# table3.net
KiCad netlist of a schematic drawn in EasyEDA
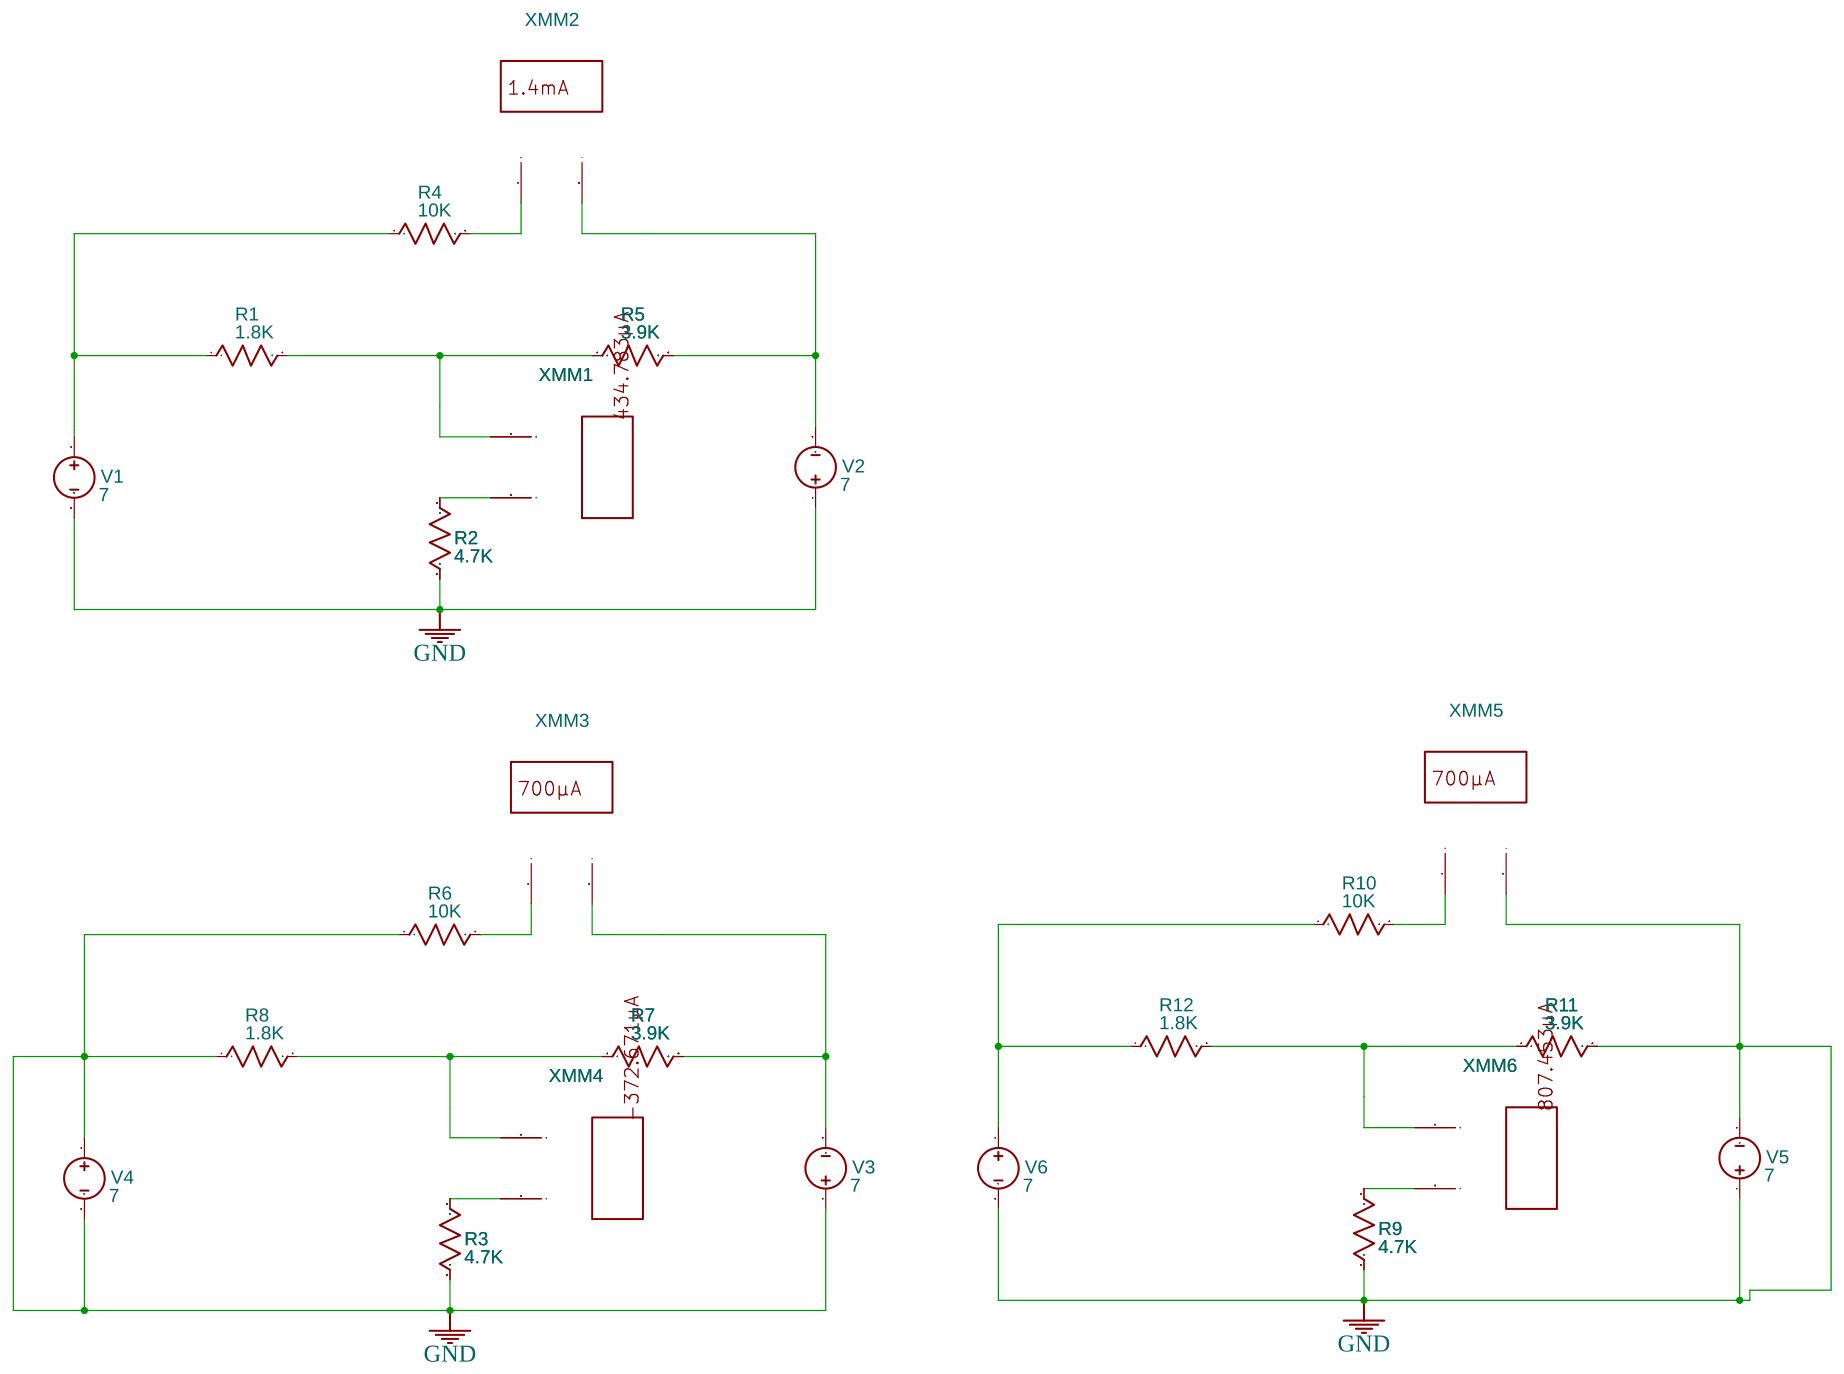
[diagram p0: schematic sheet]

(export (version "E")
  (design (tool "Eeschema 10.0.6"))
  (components
    (comp (ref "R1") (value "1.8K") (libsource (lib "") (part "Resistor_US")))
    (comp (ref "R2") (value "4.7K") (libsource (lib "") (part "Resistor_US_1")))
    (comp (ref "R3") (value "4.7K") (libsource (lib "") (part "Resistor_US_1")))
    (comp (ref "R4") (value "10K") (libsource (lib "") (part "Resistor_US")))
    (comp (ref "R5") (value "3.9K") (libsource (lib "") (part "Resistor_US")))
    (comp (ref "R6") (value "10K") (libsource (lib "") (part "Resistor_US")))
    (comp (ref "R7") (value "3.9K") (libsource (lib "") (part "Resistor_US")))
    (comp (ref "R8") (value "1.8K") (libsource (lib "") (part "Resistor_US")))
    (comp (ref "R9") (value "4.7K") (libsource (lib "") (part "Resistor_US_1")))
    (comp (ref "R10") (value "10K") (libsource (lib "") (part "Resistor_US")))
    (comp (ref "R11") (value "3.9K") (libsource (lib "") (part "Resistor_US")))
    (comp (ref "R12") (value "1.8K") (libsource (lib "") (part "Resistor_US")))
    (comp (ref "V1") (value "7") (libsource (lib "") (part "VDC_1")))
    (comp (ref "V2") (value "7") (libsource (lib "") (part "VDC")))
    (comp (ref "V3") (value "7") (libsource (lib "") (part "VDC")))
    (comp (ref "V4") (value "7") (libsource (lib "") (part "VDC_1")))
    (comp (ref "V5") (value "7") (libsource (lib "") (part "VDC")))
    (comp (ref "V6") (value "7") (libsource (lib "") (part "VDC_1")))
    (comp (ref "XMM1") (value "Multimeter") (libsource (lib "") (part "MULTIMETER_3")))
    (comp (ref "XMM2") (value "Multimeter") (libsource (lib "") (part "MULTIMETER_4")))
    (comp (ref "XMM3") (value "Multimeter") (libsource (lib "") (part "MULTIMETER_2")))
    (comp (ref "XMM4") (value "Multimeter") (libsource (lib "") (part "MULTIMETER")))
    (comp (ref "XMM5") (value "Multimeter") (libsource (lib "") (part "MULTIMETER_2")))
    (comp (ref "XMM6") (value "Multimeter") (libsource (lib "") (part "MULTIMETER_1")))
  )
  (nets
    (net (code "1") (name "GND") (class "Default")
      (node (ref "R11") (pin "2") (pinfunction "2_2") (pintype "unspecified"))
      (node (ref "R2") (pin "1") (pinfunction "1_1") (pintype "unspecified"))
      (node (ref "R3") (pin "1") (pinfunction "1_1") (pintype "unspecified"))
      (node (ref "R6") (pin "1") (pinfunction "1_1") (pintype "unspecified"))
      (node (ref "R8") (pin "1") (pinfunction "1_1") (pintype "unspecified"))
      (node (ref "R9") (pin "1") (pinfunction "1_1") (pintype "unspecified"))
      (node (ref "V1") (pin "2") (pinfunction "2_2") (pintype "unspecified"))
      (node (ref "V2") (pin "1") (pinfunction "1_1") (pintype "unspecified"))
      (node (ref "V3") (pin "1") (pinfunction "1_1") (pintype "unspecified"))
      (node (ref "V4") (pin "1") (pinfunction "1_1") (pintype "unspecified"))
      (node (ref "V4") (pin "2") (pinfunction "2_2") (pintype "unspecified"))
      (node (ref "V5") (pin "1") (pinfunction "1_1") (pintype "unspecified"))
      (node (ref "V5") (pin "2") (pinfunction "2_2") (pintype "unspecified"))
      (node (ref "V6") (pin "2") (pinfunction "2_2") (pintype "unspecified"))
      (node (ref "XMM5") (pin "2") (pinfunction "I_2") (pintype "unspecified"))
    )
    (net (code "2") (name "Net-(R1-Pad1)") (class "Default")
      (node (ref "R1") (pin "1") (pinfunction "1_1") (pintype "unspecified"))
      (node (ref "R4") (pin "1") (pinfunction "1_1") (pintype "unspecified"))
      (node (ref "V1") (pin "1") (pinfunction "1_1") (pintype "unspecified"))
    )
    (net (code "3") (name "Net-(R10-Pad1)") (class "Default")
      (node (ref "R10") (pin "1") (pinfunction "1_1") (pintype "unspecified"))
      (node (ref "R12") (pin "1") (pinfunction "1_1") (pintype "unspecified"))
      (node (ref "V6") (pin "1") (pinfunction "1_1") (pintype "unspecified"))
    )
    (net (code "4") (name "Net-(XMM1-+)") (class "Default")
      (node (ref "R1") (pin "2") (pinfunction "2_2") (pintype "unspecified"))
      (node (ref "R5") (pin "1") (pinfunction "1_1") (pintype "unspecified"))
      (node (ref "XMM1") (pin "1") (pinfunction "+_1") (pintype "unspecified"))
    )
    (net (code "5") (name "Net-(XMM1-I)") (class "Default")
      (node (ref "R2") (pin "2") (pinfunction "2_2") (pintype "unspecified"))
      (node (ref "XMM1") (pin "2") (pinfunction "I_2") (pintype "unspecified"))
    )
    (net (code "6") (name "Net-(XMM2-+)") (class "Default")
      (node (ref "R4") (pin "2") (pinfunction "2_2") (pintype "unspecified"))
      (node (ref "XMM2") (pin "1") (pinfunction "+_1") (pintype "unspecified"))
    )
    (net (code "7") (name "Net-(XMM2-I)") (class "Default")
      (node (ref "R5") (pin "2") (pinfunction "2_2") (pintype "unspecified"))
      (node (ref "V2") (pin "2") (pinfunction "2_2") (pintype "unspecified"))
      (node (ref "XMM2") (pin "2") (pinfunction "I_2") (pintype "unspecified"))
    )
    (net (code "8") (name "Net-(XMM3-+)") (class "Default")
      (node (ref "R6") (pin "2") (pinfunction "2_2") (pintype "unspecified"))
      (node (ref "XMM3") (pin "1") (pinfunction "+_1") (pintype "unspecified"))
    )
    (net (code "9") (name "Net-(XMM3-I)") (class "Default")
      (node (ref "R7") (pin "2") (pinfunction "2_2") (pintype "unspecified"))
      (node (ref "V3") (pin "2") (pinfunction "2_2") (pintype "unspecified"))
      (node (ref "XMM3") (pin "2") (pinfunction "I_2") (pintype "unspecified"))
    )
    (net (code "10") (name "Net-(XMM4-+)") (class "Default")
      (node (ref "R7") (pin "1") (pinfunction "1_1") (pintype "unspecified"))
      (node (ref "R8") (pin "2") (pinfunction "2_2") (pintype "unspecified"))
      (node (ref "XMM4") (pin "1") (pinfunction "+_1") (pintype "unspecified"))
    )
    (net (code "11") (name "Net-(XMM4-I)") (class "Default")
      (node (ref "R3") (pin "2") (pinfunction "2_2") (pintype "unspecified"))
      (node (ref "XMM4") (pin "2") (pinfunction "I_2") (pintype "unspecified"))
    )
    (net (code "12") (name "Net-(XMM5-+)") (class "Default")
      (node (ref "R10") (pin "2") (pinfunction "2_2") (pintype "unspecified"))
      (node (ref "XMM5") (pin "1") (pinfunction "+_1") (pintype "unspecified"))
    )
    (net (code "13") (name "Net-(XMM6-+)") (class "Default")
      (node (ref "R11") (pin "1") (pinfunction "1_1") (pintype "unspecified"))
      (node (ref "R12") (pin "2") (pinfunction "2_2") (pintype "unspecified"))
      (node (ref "XMM6") (pin "1") (pinfunction "+_1") (pintype "unspecified"))
    )
    (net (code "14") (name "Net-(XMM6-I)") (class "Default")
      (node (ref "R9") (pin "2") (pinfunction "2_2") (pintype "unspecified"))
      (node (ref "XMM6") (pin "2") (pinfunction "I_2") (pintype "unspecified"))
    )
  )
)
